# ATTinyRec.net
KiCad netlist of a schematic drawn in EAGLE
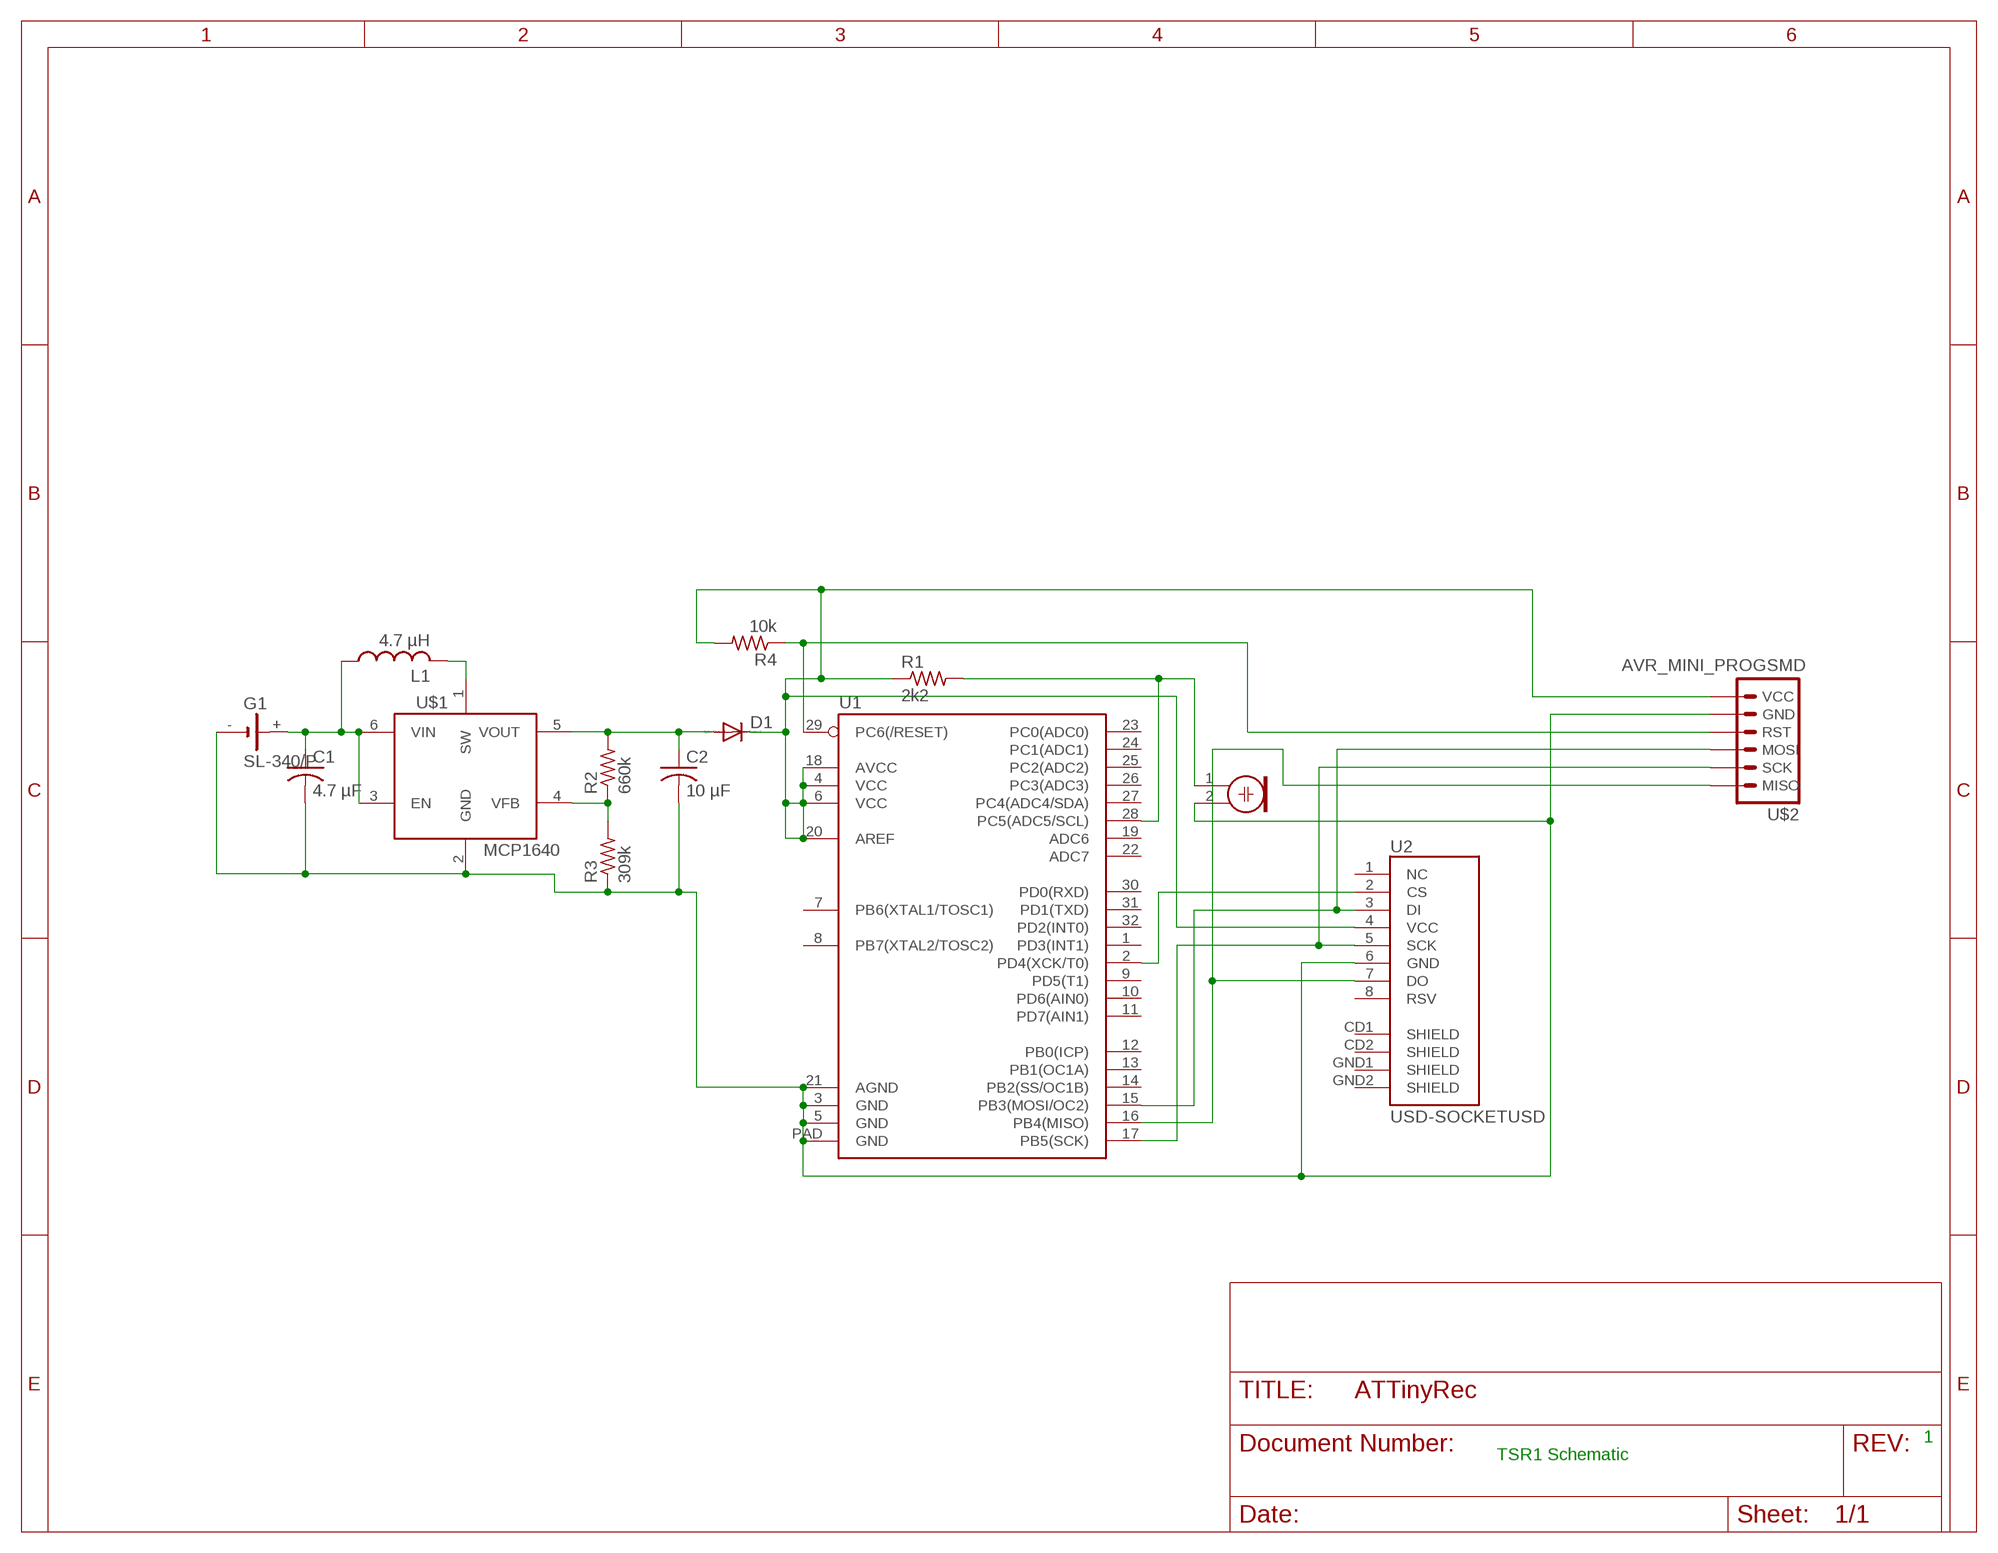
[diagram p0: schematic, sheet 1]

(export (version "E")
  (design (tool "Eeschema 10.0.6"))
  (components
    (comp (ref "C1")
      (value "4.7 µF")
      (footprint "eagle-import:C0402")
      (libsource (lib "eagle-import") (part "C-USC0402"))
    )
    (comp (ref "C2")
      (value "10 µF")
      (footprint "eagle-import:C0402")
      (libsource (lib "eagle-import") (part "C-USC0402"))
    )
    (comp (ref "D1")
      (value "DIODE-DO214AC")
      (footprint "eagle-import:DO214AC")
      (libsource (lib "eagle-import") (part "DIODE-DO214AC"))
    )
    (comp (ref "G1")
      (value "SL-340/P")
      (footprint "eagle-import:BEL_P")
      (libsource (lib "eagle-import") (part "SL-340/P"))
    )
    (comp (ref "L1")
      (value "4.7 µH")
      (footprint "eagle-import:L2012C")
      (libsource (lib "eagle-import") (part "L-USL2012C"))
    )
    (comp (ref "M1")
      (value "ELECTRET_MICROPHON-WM-62PC/62PK")
      (footprint "eagle-import:WM-62PC_62PK")
      (libsource (lib "eagle-import") (part "ELECTRET_MICROPHON-WM-62PC/62PK"))
    )
    (comp (ref "R1")
      (value "2k2")
      (footprint "eagle-import:R0402")
      (libsource (lib "eagle-import") (part "R-US_R0402"))
    )
    (comp (ref "R2")
      (value "660k")
      (footprint "eagle-import:R0402")
      (libsource (lib "eagle-import") (part "R-US_R0402"))
    )
    (comp (ref "R3")
      (value "309k")
      (footprint "eagle-import:R0402")
      (libsource (lib "eagle-import") (part "R-US_R0402"))
    )
    (comp (ref "R4")
      (value "10k")
      (footprint "eagle-import:R0402")
      (libsource (lib "eagle-import") (part "R-US_R0402"))
    )
    (comp (ref "U$1")
      (value "MCP1640")
      (footprint "eagle-import:SOT23-6")
      (libsource (lib "eagle-import") (part "MCP1640"))
    )
    (comp (ref "U$2")
      (value "AVR_MINI_PROGSMD")
      (footprint "eagle-import:AVR_MINI_PROG")
      (libsource (lib "eagle-import") (part "AVR_MINI_PROGSMD"))
    )
    (comp (ref "U1")
      (value "ATMEGA328P_MLFMLF32")
      (footprint "eagle-import:MLF32-PAD")
      (libsource (lib "eagle-import") (part "ATMEGA328P_MLFMLF32"))
    )
    (comp (ref "U2")
      (value "USD-SOCKETUSD")
      (footprint "eagle-import:USD-SOCKET-PP")
      (libsource (lib "eagle-import") (part "USD-SOCKETUSD"))
    )
  )
  (nets
    (net (code "1") (name "Net-(U$1-EN)") (class "Default")
      (node (ref "C1") (pin "1") (pinfunction "1_1") (pintype "passive"))
      (node (ref "G1") (pin "+") (pinfunction "+_+") (pintype "passive"))
      (node (ref "L1") (pin "1") (pinfunction "1_1") (pintype "passive"))
      (node (ref "U$1") (pin "3") (pinfunction "EN_3") (pintype "input"))
      (node (ref "U$1") (pin "6") (pinfunction "VIN_6") (pintype "power_in"))
    )
    (net (code "2") (name "Net-(U$1-GND)") (class "Default")
      (node (ref "C1") (pin "2") (pinfunction "2_2") (pintype "passive"))
      (node (ref "C2") (pin "2") (pinfunction "2_2") (pintype "passive"))
      (node (ref "G1") (pin "-") (pinfunction "-_-") (pintype "passive"))
      (node (ref "M1") (pin "2") (pinfunction "2_2") (pintype "passive"))
      (node (ref "R3") (pin "1") (pinfunction "1_1") (pintype "passive"))
      (node (ref "U$1") (pin "2") (pinfunction "GND_2") (pintype "power_in"))
      (node (ref "U$2") (pin "2") (pinfunction "GND_2") (pintype "passive"))
      (node (ref "U1") (pin "21") (pinfunction "AGND_21") (pintype "bidirectional"))
      (node (ref "U1") (pin "3") (pinfunction "GND_3") (pintype "bidirectional"))
      (node (ref "U1") (pin "5") (pinfunction "GND_5") (pintype "bidirectional"))
      (node (ref "U1") (pin "PAD") (pinfunction "GND_PAD") (pintype "bidirectional"))
      (node (ref "U2") (pin "6") (pinfunction "GND_6") (pintype "bidirectional"))
    )
    (net (code "3") (name "Net-(U$1-SW)") (class "Default")
      (node (ref "L1") (pin "2") (pinfunction "2_2") (pintype "passive"))
      (node (ref "U$1") (pin "1") (pinfunction "SW_1") (pintype "passive"))
    )
    (net (code "4") (name "Net-(U$1-VFB)") (class "Default")
      (node (ref "R2") (pin "1") (pinfunction "1_1") (pintype "passive"))
      (node (ref "R3") (pin "2") (pinfunction "2_2") (pintype "passive"))
      (node (ref "U$1") (pin "4") (pinfunction "VFB_4") (pintype "input"))
    )
    (net (code "5") (name "Net-(U$1-VOUT)") (class "Default")
      (node (ref "C2") (pin "1") (pinfunction "1_1") (pintype "passive"))
      (node (ref "D1") (pin "A") (pinfunction "A_A") (pintype "passive"))
      (node (ref "R2") (pin "2") (pinfunction "2_2") (pintype "passive"))
      (node (ref "U$1") (pin "5") (pinfunction "VOUT_5") (pintype "power_in"))
    )
    (net (code "6") (name "Net-(U$2-MISO)") (class "Default")
      (node (ref "U$2") (pin "6") (pinfunction "MISO_6") (pintype "passive"))
      (node (ref "U1") (pin "16") (pinfunction "PB4(MISO)_16") (pintype "bidirectional"))
      (node (ref "U2") (pin "7") (pinfunction "DO_7") (pintype "bidirectional"))
    )
    (net (code "7") (name "Net-(U$2-MOSI)") (class "Default")
      (node (ref "U$2") (pin "4") (pinfunction "MOSI_4") (pintype "passive"))
      (node (ref "U1") (pin "15") (pinfunction "PB3(MOSI/OC2)_15") (pintype "bidirectional"))
      (node (ref "U2") (pin "3") (pinfunction "DI_3") (pintype "bidirectional"))
    )
    (net (code "8") (name "Net-(U$2-RST)") (class "Default")
      (node (ref "R4") (pin "1") (pinfunction "1_1") (pintype "passive"))
      (node (ref "U$2") (pin "3") (pinfunction "RST_3") (pintype "passive"))
      (node (ref "U1") (pin "29") (pinfunction "PC6(/RESET)_29") (pintype "bidirectional"))
    )
    (net (code "9") (name "Net-(U$2-SCK)") (class "Default")
      (node (ref "U$2") (pin "5") (pinfunction "SCK_5") (pintype "passive"))
      (node (ref "U1") (pin "17") (pinfunction "PB5(SCK)_17") (pintype "bidirectional"))
      (node (ref "U2") (pin "5") (pinfunction "SCK_5") (pintype "bidirectional"))
    )
    (net (code "10") (name "Net-(U$2-VCC)") (class "Default")
      (node (ref "D1") (pin "C") (pinfunction "C_C") (pintype "passive"))
      (node (ref "R1") (pin "1") (pinfunction "1_1") (pintype "passive"))
      (node (ref "R4") (pin "2") (pinfunction "2_2") (pintype "passive"))
      (node (ref "U$2") (pin "1") (pinfunction "VCC_1") (pintype "passive"))
      (node (ref "U1") (pin "18") (pinfunction "AVCC_18") (pintype "bidirectional"))
      (node (ref "U1") (pin "20") (pinfunction "AREF_20") (pintype "bidirectional"))
      (node (ref "U1") (pin "4") (pinfunction "VCC_4") (pintype "bidirectional"))
      (node (ref "U1") (pin "6") (pinfunction "VCC_6") (pintype "bidirectional"))
      (node (ref "U2") (pin "4") (pinfunction "VCC_4") (pintype "bidirectional"))
    )
    (net (code "11") (name "Net-(U1-PC5(ADC5{slash}SCL))") (class "Default")
      (node (ref "M1") (pin "1") (pinfunction "1_1") (pintype "passive"))
      (node (ref "R1") (pin "2") (pinfunction "2_2") (pintype "passive"))
      (node (ref "U1") (pin "28") (pinfunction "PC5(ADC5/SCL)_28") (pintype "bidirectional"))
    )
    (net (code "12") (name "Net-(U1-PD4(XCK{slash}T0))") (class "Default")
      (node (ref "U1") (pin "2") (pinfunction "PD4(XCK/T0)_2") (pintype "bidirectional"))
      (node (ref "U2") (pin "2") (pinfunction "CS_2") (pintype "bidirectional"))
    )
    (net (code "13") (name "unconnected-(U1-ADC6-Pad19)") (class "Default")
      (node (ref "U1") (pin "19") (pinfunction "ADC6_19") (pintype "bidirectional"))
    )
    (net (code "14") (name "unconnected-(U1-ADC7-Pad22)") (class "Default")
      (node (ref "U1") (pin "22") (pinfunction "ADC7_22") (pintype "bidirectional"))
    )
    (net (code "15") (name "unconnected-(U1-PB0(ICP)-Pad12)") (class "Default")
      (node (ref "U1") (pin "12") (pinfunction "PB0(ICP)_12") (pintype "bidirectional"))
    )
    (net (code "16") (name "unconnected-(U1-PB1(OC1A)-Pad13)") (class "Default")
      (node (ref "U1") (pin "13") (pinfunction "PB1(OC1A)_13") (pintype "bidirectional"))
    )
    (net (code "17") (name "unconnected-(U1-PB2(SS{slash}OC1B)-Pad14)") (class "Default")
      (node (ref "U1") (pin "14") (pinfunction "PB2(SS/OC1B)_14") (pintype "bidirectional"))
    )
    (net (code "18") (name "unconnected-(U1-PB6(XTAL1{slash}TOSC1)-Pad7)") (class "Default")
      (node (ref "U1") (pin "7") (pinfunction "PB6(XTAL1/TOSC1)_7") (pintype "bidirectional"))
    )
    (net (code "19") (name "unconnected-(U1-PB7(XTAL2{slash}TOSC2)-Pad8)") (class "Default")
      (node (ref "U1") (pin "8") (pinfunction "PB7(XTAL2/TOSC2)_8") (pintype "bidirectional"))
    )
    (net (code "20") (name "unconnected-(U1-PC0(ADC0)-Pad23)") (class "Default")
      (node (ref "U1") (pin "23") (pinfunction "PC0(ADC0)_23") (pintype "bidirectional"))
    )
    (net (code "21") (name "unconnected-(U1-PC1(ADC1)-Pad24)") (class "Default")
      (node (ref "U1") (pin "24") (pinfunction "PC1(ADC1)_24") (pintype "bidirectional"))
    )
    (net (code "22") (name "unconnected-(U1-PC2(ADC2)-Pad25)") (class "Default")
      (node (ref "U1") (pin "25") (pinfunction "PC2(ADC2)_25") (pintype "bidirectional"))
    )
    (net (code "23") (name "unconnected-(U1-PC3(ADC3)-Pad26)") (class "Default")
      (node (ref "U1") (pin "26") (pinfunction "PC3(ADC3)_26") (pintype "bidirectional"))
    )
    (net (code "24") (name "unconnected-(U1-PC4(ADC4{slash}SDA)-Pad27)") (class "Default")
      (node (ref "U1") (pin "27") (pinfunction "PC4(ADC4/SDA)_27") (pintype "bidirectional"))
    )
    (net (code "25") (name "unconnected-(U1-PD0(RXD)-Pad30)") (class "Default")
      (node (ref "U1") (pin "30") (pinfunction "PD0(RXD)_30") (pintype "bidirectional"))
    )
    (net (code "26") (name "unconnected-(U1-PD1(TXD)-Pad31)") (class "Default")
      (node (ref "U1") (pin "31") (pinfunction "PD1(TXD)_31") (pintype "bidirectional"))
    )
    (net (code "27") (name "unconnected-(U1-PD2(INT0)-Pad32)") (class "Default")
      (node (ref "U1") (pin "32") (pinfunction "PD2(INT0)_32") (pintype "bidirectional"))
    )
    (net (code "28") (name "unconnected-(U1-PD3(INT1)-Pad1)") (class "Default")
      (node (ref "U1") (pin "1") (pinfunction "PD3(INT1)_1") (pintype "bidirectional"))
    )
    (net (code "29") (name "unconnected-(U1-PD5(T1)-Pad9)") (class "Default")
      (node (ref "U1") (pin "9") (pinfunction "PD5(T1)_9") (pintype "bidirectional"))
    )
    (net (code "30") (name "unconnected-(U1-PD6(AIN0)-Pad10)") (class "Default")
      (node (ref "U1") (pin "10") (pinfunction "PD6(AIN0)_10") (pintype "bidirectional"))
    )
    (net (code "31") (name "unconnected-(U1-PD7(AIN1)-Pad11)") (class "Default")
      (node (ref "U1") (pin "11") (pinfunction "PD7(AIN1)_11") (pintype "bidirectional"))
    )
    (net (code "32") (name "unconnected-(U2-NC-Pad1)") (class "Default")
      (node (ref "U2") (pin "1") (pinfunction "NC_1") (pintype "bidirectional"))
    )
    (net (code "33") (name "unconnected-(U2-RSV-Pad8)") (class "Default")
      (node (ref "U2") (pin "8") (pinfunction "RSV_8") (pintype "bidirectional"))
    )
    (net (code "34") (name "unconnected-(U2-SHIELD-PadCD1)") (class "Default")
      (node (ref "U2") (pin "CD1") (pinfunction "SHIELD_CD1") (pintype "bidirectional"))
    )
    (net (code "35") (name "unconnected-(U2-SHIELD-PadCD2)") (class "Default")
      (node (ref "U2") (pin "CD2") (pinfunction "SHIELD_CD2") (pintype "bidirectional"))
    )
    (net (code "36") (name "unconnected-(U2-SHIELD-PadGND1)") (class "Default")
      (node (ref "U2") (pin "GND1") (pinfunction "SHIELD_GND1") (pintype "bidirectional"))
    )
    (net (code "37") (name "unconnected-(U2-SHIELD-PadGND2)") (class "Default")
      (node (ref "U2") (pin "GND2") (pinfunction "SHIELD_GND2") (pintype "bidirectional"))
    )
  )
)
